# pot-boardC.net
KiCad netlist of a schematic drawn in EAGLE
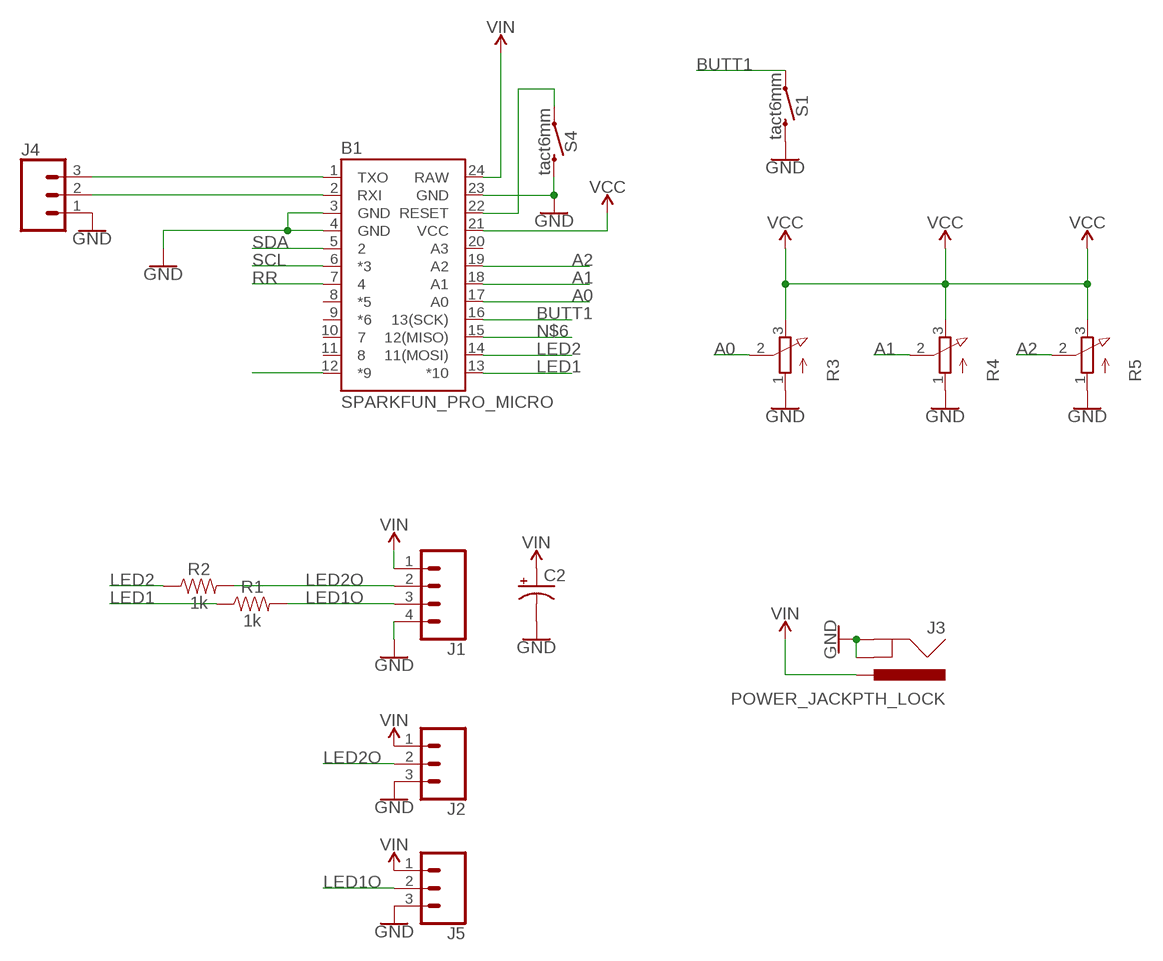
[diagram p0: schematic, sheet 1]

(export (version "E")
  (design (tool "Eeschema 10.0.6"))
  (components
    (comp (ref "B1")
      (value "SPARKFUN_PRO_MICRO")
      (footprint "eagle-import:SPARKFUN_PRO_MICRO")
      (libsource (lib "eagle-import") (part "SPARKFUN_PRO_MICRO"))
    )
    (comp (ref "C2")
      (value "CPOL-USE3.5-8")
      (footprint "eagle-import:E3,5-8")
      (libsource (lib "eagle-import") (part "CPOL-USE3.5-8"))
    )
    (comp (ref "J1")
      (value "CONN_04")
      (footprint "eagle-import:1X04")
      (libsource (lib "eagle-import") (part "CONN_04"))
    )
    (comp (ref "J2")
      (value "CONN_03")
      (footprint "eagle-import:1X03")
      (libsource (lib "eagle-import") (part "CONN_03"))
    )
    (comp (ref "J3")
      (value "POWER_JACKPTH_LOCK")
      (footprint "eagle-import:POWER_JACK_PTH_LOCK")
      (libsource (lib "eagle-import") (part "POWER_JACKPTH_LOCK"))
    )
    (comp (ref "J4")
      (value "CONN_03")
      (footprint "eagle-import:1X03")
      (libsource (lib "eagle-import") (part "CONN_03"))
    )
    (comp (ref "J5")
      (value "CONN_03")
      (footprint "eagle-import:1X03")
      (libsource (lib "eagle-import") (part "CONN_03"))
    )
    (comp (ref "R1")
      (value "1k")
      (footprint "eagle-import:AXIAL-0.3")
      (libsource (lib "eagle-import") (part "1KOHM-HORIZ-1/4W-5%"))
    )
    (comp (ref "R2")
      (value "1k")
      (footprint "eagle-import:AXIAL-0.3")
      (libsource (lib "eagle-import") (part "1KOHM-HORIZ-1/4W-5%"))
    )
    (comp (ref "R3")
      (value "3RP/1610N")
      (footprint "eagle-import:3RP_1610N")
      (libsource (lib "eagle-import") (part "3RP/1610N"))
    )
    (comp (ref "R4")
      (value "3RP/1610N")
      (footprint "eagle-import:3RP_1610N")
      (libsource (lib "eagle-import") (part "3RP/1610N"))
    )
    (comp (ref "R5")
      (value "3RP/1610N")
      (footprint "eagle-import:3RP_1610N")
      (libsource (lib "eagle-import") (part "3RP/1610N"))
    )
    (comp (ref "S1")
      (value "tact6mm")
      (footprint "eagle-import:TACTILE_SWITCH_PTH_6.0MM")
      (libsource (lib "eagle-import") (part "MOMENTARY-SWITCH-SPST-PTH-6.0MM"))
    )
    (comp (ref "S4")
      (value "tact6mm")
      (footprint "eagle-import:TACTILE_SWITCH_PTH_6.0MM")
      (libsource (lib "eagle-import") (part "MOMENTARY-SWITCH-SPST-PTH-6.0MM"))
    )
  )
  (nets
    (net (code "1") (name "/A0") (class "Default")
      (node (ref "B1") (pin "17") (pinfunction "A0_17") (pintype "bidirectional"))
      (node (ref "R3") (pin "2") (pinfunction "S_2") (pintype "passive"))
    )
    (net (code "2") (name "/A1") (class "Default")
      (node (ref "B1") (pin "18") (pinfunction "A1_18") (pintype "bidirectional"))
      (node (ref "R4") (pin "2") (pinfunction "S_2") (pintype "passive"))
    )
    (net (code "3") (name "/A2") (class "Default")
      (node (ref "B1") (pin "19") (pinfunction "A2_19") (pintype "bidirectional"))
      (node (ref "R5") (pin "2") (pinfunction "S_2") (pintype "passive"))
    )
    (net (code "4") (name "/BUTT1") (class "Default")
      (node (ref "B1") (pin "16") (pinfunction "13(SCK)_16") (pintype "bidirectional"))
      (node (ref "S1") (pin "1") (pinfunction "1_1") (pintype "passive"))
    )
    (net (code "5") (name "/LED1") (class "Default")
      (node (ref "B1") (pin "13") (pinfunction "*10_13") (pintype "bidirectional"))
      (node (ref "R1") (pin "P$1") (pinfunction "1_P$1") (pintype "passive"))
    )
    (net (code "6") (name "/LED1O") (class "Default")
      (node (ref "J1") (pin "3") (pinfunction "3_3") (pintype "passive"))
      (node (ref "J5") (pin "2") (pinfunction "2_2") (pintype "passive"))
      (node (ref "R1") (pin "P$2") (pinfunction "2_P$2") (pintype "passive"))
    )
    (net (code "7") (name "/LED2") (class "Default")
      (node (ref "B1") (pin "14") (pinfunction "11(MOSI)_14") (pintype "bidirectional"))
      (node (ref "R2") (pin "P$1") (pinfunction "1_P$1") (pintype "passive"))
    )
    (net (code "8") (name "/LED2O") (class "Default")
      (node (ref "J1") (pin "2") (pinfunction "2_2") (pintype "passive"))
      (node (ref "J2") (pin "2") (pinfunction "2_2") (pintype "passive"))
      (node (ref "R2") (pin "P$2") (pinfunction "2_P$2") (pintype "passive"))
    )
    (net (code "9") (name "/N$6") (class "Default")
      (node (ref "B1") (pin "15") (pinfunction "12(MISO)_15") (pintype "bidirectional"))
    )
    (net (code "10") (name "/RR") (class "Default")
      (node (ref "B1") (pin "7") (pinfunction "4_7") (pintype "bidirectional"))
    )
    (net (code "11") (name "/SCL") (class "Default")
      (node (ref "B1") (pin "6") (pinfunction "*3_6") (pintype "bidirectional"))
    )
    (net (code "12") (name "/SDA") (class "Default")
      (node (ref "B1") (pin "5") (pinfunction "2_5") (pintype "bidirectional"))
    )
    (net (code "13") (name "GND") (class "Default")
      (node (ref "B1") (pin "23") (pinfunction "GND_23") (pintype "power_in"))
      (node (ref "B1") (pin "3") (pinfunction "GND_3") (pintype "power_in"))
      (node (ref "B1") (pin "4") (pinfunction "GND_4") (pintype "power_in"))
      (node (ref "C2") (pin "-") (pinfunction "-_-") (pintype "passive"))
      (node (ref "J1") (pin "4") (pinfunction "4_4") (pintype "passive"))
      (node (ref "J2") (pin "3") (pinfunction "3_3") (pintype "passive"))
      (node (ref "J3") (pin "GND") (pinfunction "GND_GND") (pintype "bidirectional"))
      (node (ref "J3") (pin "GNDBREAK") (pinfunction "GNDBREAK_GNDBREAK") (pintype "bidirectional"))
      (node (ref "J4") (pin "1") (pinfunction "1_1") (pintype "passive"))
      (node (ref "J5") (pin "3") (pinfunction "3_3") (pintype "passive"))
      (node (ref "R3") (pin "1") (pinfunction "A_1") (pintype "passive"))
      (node (ref "R4") (pin "1") (pinfunction "A_1") (pintype "passive"))
      (node (ref "R5") (pin "1") (pinfunction "A_1") (pintype "passive"))
      (node (ref "S1") (pin "3") (pinfunction "2_3") (pintype "passive"))
      (node (ref "S4") (pin "3") (pinfunction "2_3") (pintype "passive"))
    )
    (net (code "14") (name "Net-(B1-RESET)") (class "Default")
      (node (ref "B1") (pin "22") (pinfunction "RESET_22") (pintype "bidirectional"))
      (node (ref "S4") (pin "1") (pinfunction "1_1") (pintype "passive"))
    )
    (net (code "15") (name "Net-(B1-RXI)") (class "Default")
      (node (ref "B1") (pin "2") (pinfunction "RXI_2") (pintype "bidirectional"))
      (node (ref "J4") (pin "2") (pinfunction "2_2") (pintype "passive"))
    )
    (net (code "16") (name "Net-(B1-TXO)") (class "Default")
      (node (ref "B1") (pin "1") (pinfunction "TXO_1") (pintype "bidirectional"))
      (node (ref "J4") (pin "3") (pinfunction "3_3") (pintype "passive"))
    )
    (net (code "17") (name "VCC") (class "Default")
      (node (ref "B1") (pin "21") (pinfunction "VCC_21") (pintype "power_in"))
      (node (ref "R3") (pin "3") (pinfunction "E_3") (pintype "passive"))
      (node (ref "R4") (pin "3") (pinfunction "E_3") (pintype "passive"))
      (node (ref "R5") (pin "3") (pinfunction "E_3") (pintype "passive"))
    )
    (net (code "18") (name "VIN") (class "Default")
      (node (ref "B1") (pin "24") (pinfunction "RAW_24") (pintype "power_in"))
      (node (ref "C2") (pin "+") (pinfunction "+_+") (pintype "passive"))
      (node (ref "J1") (pin "1") (pinfunction "1_1") (pintype "passive"))
      (node (ref "J2") (pin "1") (pinfunction "1_1") (pintype "passive"))
      (node (ref "J3") (pin "PWR") (pinfunction "PWR_PWR") (pintype "bidirectional"))
      (node (ref "J5") (pin "1") (pinfunction "1_1") (pintype "passive"))
    )
    (net (code "19") (name "unconnected-(B1-*5-Pad8)") (class "Default")
      (node (ref "B1") (pin "8") (pinfunction "*5_8") (pintype "bidirectional"))
    )
    (net (code "20") (name "unconnected-(B1-*6-Pad9)") (class "Default")
      (node (ref "B1") (pin "9") (pinfunction "*6_9") (pintype "bidirectional"))
    )
    (net (code "21") (name "unconnected-(B1-*9-Pad12)") (class "Default")
      (node (ref "B1") (pin "12") (pinfunction "*9_12") (pintype "bidirectional"))
    )
    (net (code "22") (name "unconnected-(B1-7-Pad10)") (class "Default")
      (node (ref "B1") (pin "10") (pinfunction "7_10") (pintype "bidirectional"))
    )
    (net (code "23") (name "unconnected-(B1-8-Pad11)") (class "Default")
      (node (ref "B1") (pin "11") (pinfunction "8_11") (pintype "bidirectional"))
    )
    (net (code "24") (name "unconnected-(B1-A3-Pad20)") (class "Default")
      (node (ref "B1") (pin "20") (pinfunction "A3_20") (pintype "bidirectional"))
    )
  )
)
